# RC-BoatController-Schematic-EASYEDA.net
KiCad netlist of a schematic drawn in EasyEDA
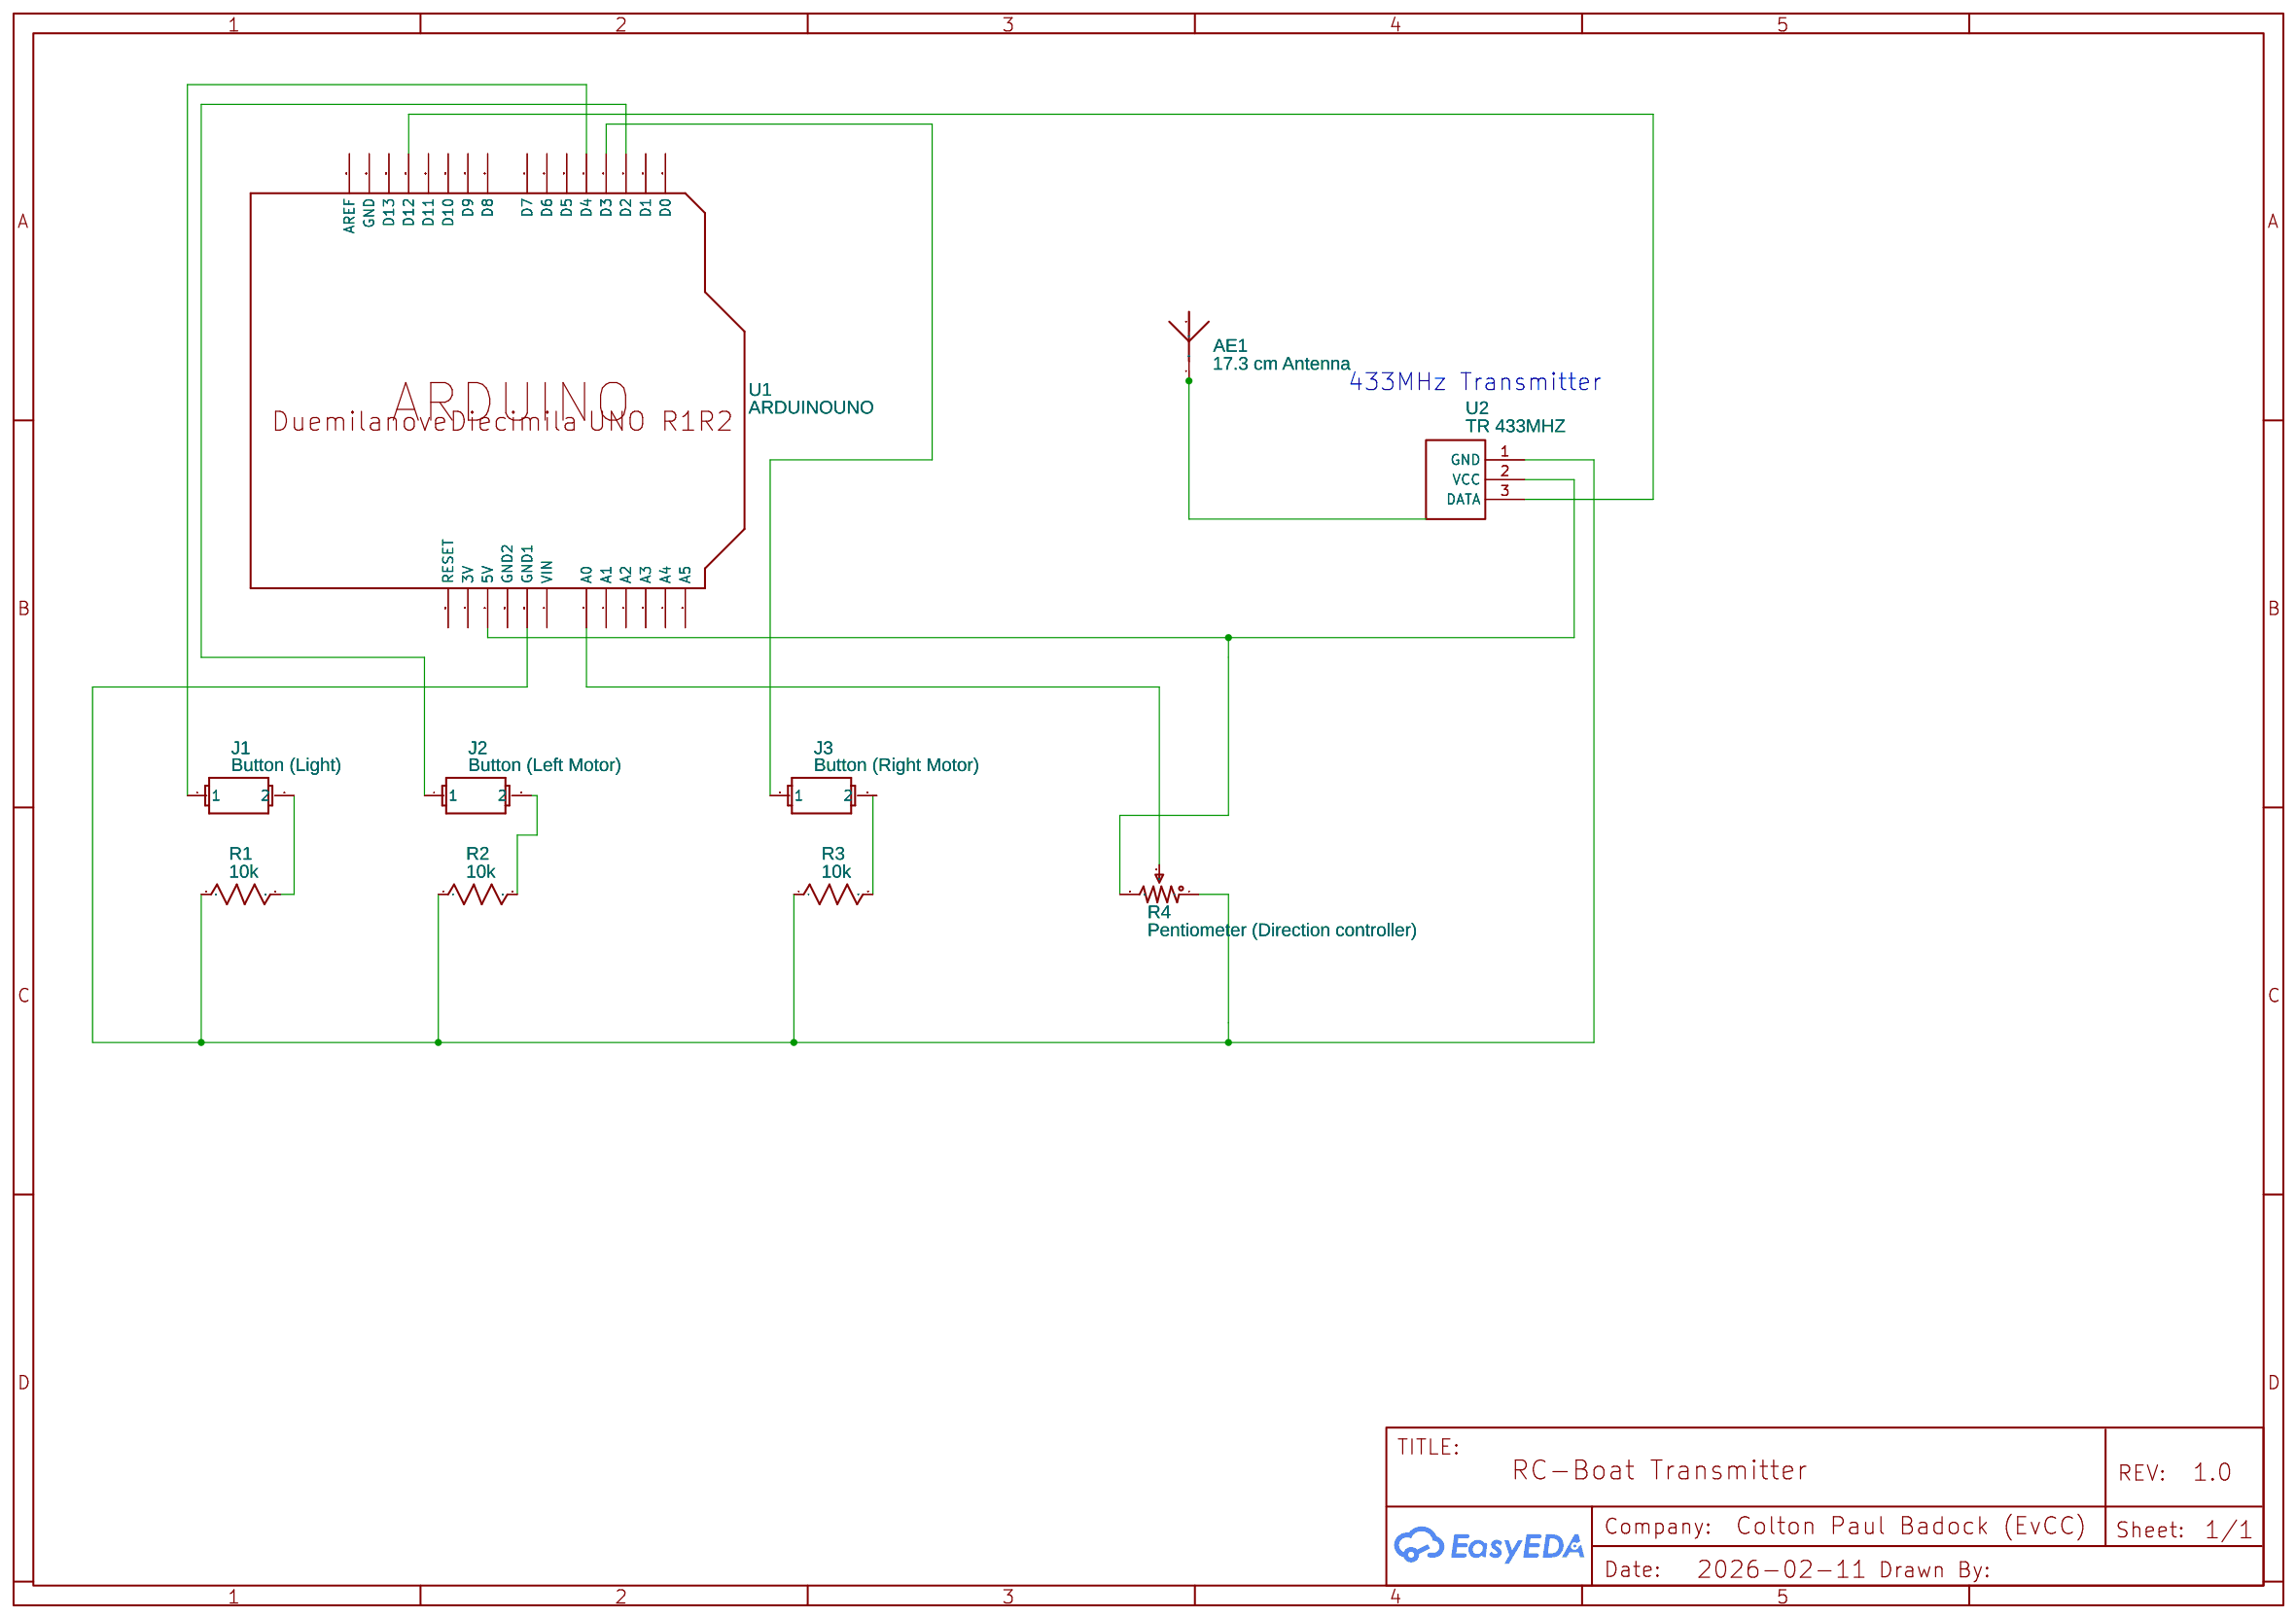
[diagram p0: schematic sheet]

(export (version "E")
  (design (tool "Eeschema 10.0.6"))
  (components
    (comp (ref "AE1")
      (value "17.3 cm Antenna")
      (fields
        (field (name "Manufacturer Part") "2450AT18A100E")
        (field (name "Manufacturer") "JOHANSON(约翰逊)")
      )
      (libsource (lib "") (part "2450AT18A100E"))
    )
    (comp (ref "J1") (value "Button (Light)") (libsource (lib "") (part "BUTTON_TD1183SA_BUTTON_TD1183SA")))
    (comp (ref "J2")
      (value "Button (Left Motor)")
      (libsource (lib "") (part "BUTTON_TD1183SA_BUTTON_TD1183SA"))
    )
    (comp (ref "J3")
      (value "Button (Right Motor)")
      (libsource (lib "") (part "BUTTON_TD1183SA_BUTTON_TD1183SA"))
    )
    (comp (ref "R1") (value "10k") (libsource (lib "") (part "R_0603_US")))
    (comp (ref "R2") (value "10k") (libsource (lib "") (part "R_0603_US")))
    (comp (ref "R3") (value "10k") (libsource (lib "") (part "R_0603_US")))
    (comp (ref "R4")
      (value "Pentiometer (Direction controller)")
      (fields
        (field (name "Manufacturer Part") "3266P-1-203")
        (field (name "Manufacturer") "Chengdu Guosheng Tech")
      )
      (libsource (lib "") (part "Pentiometer 2.0"))
    )
    (comp (ref "U1") (value "ARDUINOUNO") (libsource (lib "") (part "ARDUINOUNO")))
    (comp (ref "U2") (value "TR 433MHZ") (libsource (lib "") (part "TR 433MHZ")))
  )
  (nets
    (net (code "1") (name "Net-(J1-Pad1)") (class "Default")
      (node (ref "J1") (pin "1") (pinfunction "1_1") (pintype "unspecified"))
      (node (ref "U1") (pin "D4") (pinfunction "D4_D4") (pintype "unspecified"))
    )
    (net (code "2") (name "Net-(J1-Pad2)") (class "Default")
      (node (ref "J1") (pin "2") (pinfunction "2_2") (pintype "unspecified"))
      (node (ref "R1") (pin "2") (pinfunction "2_2") (pintype "unspecified"))
    )
    (net (code "3") (name "Net-(J2-Pad1)") (class "Default")
      (node (ref "J2") (pin "1") (pinfunction "1_1") (pintype "unspecified"))
      (node (ref "U1") (pin "D2") (pinfunction "D2_D2") (pintype "unspecified"))
    )
    (net (code "4") (name "Net-(J2-Pad2)") (class "Default")
      (node (ref "J2") (pin "2") (pinfunction "2_2") (pintype "unspecified"))
      (node (ref "R2") (pin "2") (pinfunction "2_2") (pintype "unspecified"))
    )
    (net (code "5") (name "Net-(J3-Pad1)") (class "Default")
      (node (ref "J3") (pin "1") (pinfunction "1_1") (pintype "unspecified"))
      (node (ref "U1") (pin "D3") (pinfunction "D3_D3") (pintype "unspecified"))
    )
    (net (code "6") (name "Net-(J3-Pad2)") (class "Default")
      (node (ref "J3") (pin "2") (pinfunction "2_2") (pintype "unspecified"))
      (node (ref "R3") (pin "2") (pinfunction "2_2") (pintype "unspecified"))
    )
    (net (code "7") (name "Net-(R4-Pad2)") (class "Default")
      (node (ref "R4") (pin "2") (pinfunction "2_2") (pintype "unspecified"))
      (node (ref "U1") (pin "A0") (pinfunction "A0_A0") (pintype "unspecified"))
    )
    (net (code "8") (name "Net-(U2-DATA)") (class "Default")
      (node (ref "U1") (pin "D12") (pinfunction "D12_D12") (pintype "unspecified"))
      (node (ref "U2") (pin "3") (pinfunction "DATA_3") (pintype "unspecified"))
    )
    (net (code "9") (name "Net-(U2-GND)") (class "Default")
      (node (ref "R1") (pin "1") (pinfunction "1_1") (pintype "unspecified"))
      (node (ref "R2") (pin "1") (pinfunction "1_1") (pintype "unspecified"))
      (node (ref "R3") (pin "1") (pinfunction "1_1") (pintype "unspecified"))
      (node (ref "R4") (pin "1") (pinfunction "1_1") (pintype "unspecified"))
      (node (ref "U1") (pin "GND1") (pinfunction "GND1_GND1") (pintype "passive"))
      (node (ref "U2") (pin "1") (pinfunction "GND_1") (pintype "unspecified"))
    )
    (net (code "10") (name "Net-(U2-VCC)") (class "Default")
      (node (ref "R4") (pin "3") (pinfunction "3_3") (pintype "unspecified"))
      (node (ref "U1") (pin "5V") (pinfunction "5V_5V") (pintype "passive"))
      (node (ref "U2") (pin "2") (pinfunction "VCC_2") (pintype "unspecified"))
    )
    (net (code "11") (name "unconnected-(AE1-ANT-Pad1)") (class "Default")
      (node (ref "AE1") (pin "1") (pinfunction "ANT_1") (pintype "unspecified"))
    )
    (net (code "12") (name "unconnected-(AE1-Pad2)") (class "Default")
      (node (ref "AE1") (pin "2") (pinfunction "2_2") (pintype "unspecified"))
    )
    (net (code "13") (name "unconnected-(U1-Pad3V)") (class "Default")
      (node (ref "U1") (pin "3V") (pinfunction "3V_3V") (pintype "passive"))
    )
    (net (code "14") (name "unconnected-(U1-PadA1)") (class "Default")
      (node (ref "U1") (pin "A1") (pinfunction "A1_A1") (pintype "unspecified"))
    )
    (net (code "15") (name "unconnected-(U1-PadA2)") (class "Default")
      (node (ref "U1") (pin "A2") (pinfunction "A2_A2") (pintype "unspecified"))
    )
    (net (code "16") (name "unconnected-(U1-PadA3)") (class "Default")
      (node (ref "U1") (pin "A3") (pinfunction "A3_A3") (pintype "unspecified"))
    )
    (net (code "17") (name "unconnected-(U1-PadA4)") (class "Default")
      (node (ref "U1") (pin "A4") (pinfunction "A4_A4") (pintype "unspecified"))
    )
    (net (code "18") (name "unconnected-(U1-PadA5)") (class "Default")
      (node (ref "U1") (pin "A5") (pinfunction "A5_A5") (pintype "unspecified"))
    )
    (net (code "19") (name "unconnected-(U1-PadAREF)") (class "Default")
      (node (ref "U1") (pin "AREF") (pinfunction "AREF_AREF") (pintype "unspecified"))
    )
    (net (code "20") (name "unconnected-(U1-PadD0)") (class "Default")
      (node (ref "U1") (pin "D0") (pinfunction "D0_D0") (pintype "unspecified"))
    )
    (net (code "21") (name "unconnected-(U1-PadD1)") (class "Default")
      (node (ref "U1") (pin "D1") (pinfunction "D1_D1") (pintype "unspecified"))
    )
    (net (code "22") (name "unconnected-(U1-PadD5)") (class "Default")
      (node (ref "U1") (pin "D5") (pinfunction "D5_D5") (pintype "unspecified"))
    )
    (net (code "23") (name "unconnected-(U1-PadD6)") (class "Default")
      (node (ref "U1") (pin "D6") (pinfunction "D6_D6") (pintype "unspecified"))
    )
    (net (code "24") (name "unconnected-(U1-PadD7)") (class "Default")
      (node (ref "U1") (pin "D7") (pinfunction "D7_D7") (pintype "unspecified"))
    )
    (net (code "25") (name "unconnected-(U1-PadD8)") (class "Default")
      (node (ref "U1") (pin "D8") (pinfunction "D8_D8") (pintype "unspecified"))
    )
    (net (code "26") (name "unconnected-(U1-PadD9)") (class "Default")
      (node (ref "U1") (pin "D9") (pinfunction "D9_D9") (pintype "unspecified"))
    )
    (net (code "27") (name "unconnected-(U1-PadD10)") (class "Default")
      (node (ref "U1") (pin "D10") (pinfunction "D10_D10") (pintype "unspecified"))
    )
    (net (code "28") (name "unconnected-(U1-PadD11)") (class "Default")
      (node (ref "U1") (pin "D11") (pinfunction "D11_D11") (pintype "unspecified"))
    )
    (net (code "29") (name "unconnected-(U1-PadD13)") (class "Default")
      (node (ref "U1") (pin "D13") (pinfunction "D13_D13") (pintype "unspecified"))
    )
    (net (code "30") (name "unconnected-(U1-PadGND)") (class "Default")
      (node (ref "U1") (pin "GND") (pinfunction "GND_GND") (pintype "passive"))
    )
    (net (code "31") (name "unconnected-(U1-PadGND2)") (class "Default")
      (node (ref "U1") (pin "GND2") (pinfunction "GND2_GND2") (pintype "passive"))
    )
    (net (code "32") (name "unconnected-(U1-PadRESET)") (class "Default")
      (node (ref "U1") (pin "RESET") (pinfunction "RESET_RESET") (pintype "unspecified"))
    )
    (net (code "33") (name "unconnected-(U1-PadVIN)") (class "Default")
      (node (ref "U1") (pin "VIN") (pinfunction "VIN_VIN") (pintype "passive"))
    )
  )
)
